# power-1.net
KiCad netlist of a schematic drawn in Altium Designer
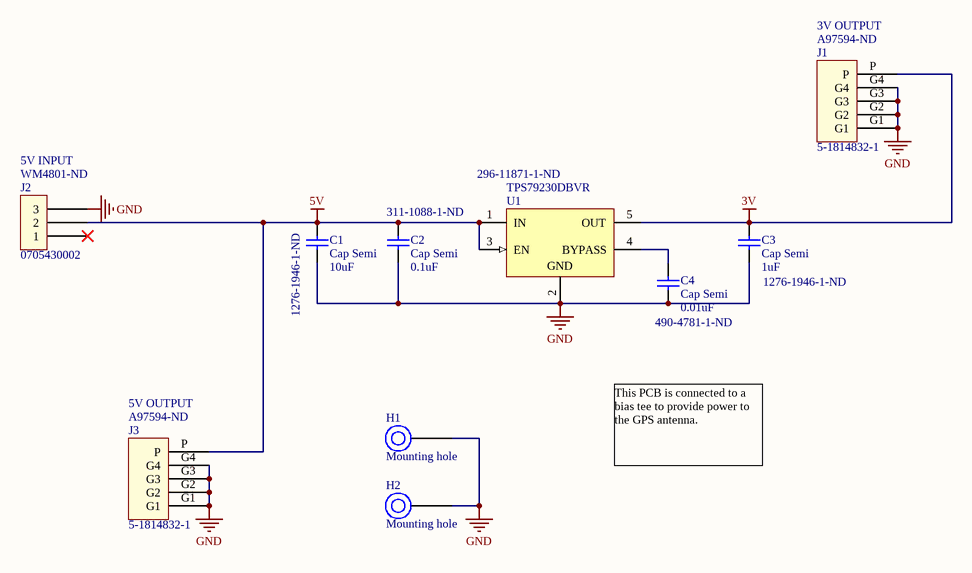
[diagram p0: power-1.SchDoc]

(export (version "E")
  (design (tool "Eeschema 10.0.6"))
  (components
    (comp (ref "C1")
      (value "Cap Semi")
      (footprint "1608[0603]")
      (description "Capacitor (Semiconductor SIM Model)")
      (fields
        (field (name "ALTIUM_VALUE") "10uF")
        (field (name "SUPPLIER PART NUMBER 1") "1276-1946-1-ND")
        (field (name "MANUFACTURER") "Samsung")
        (field (name "MANUFACTURER PART NUMBER") "CL10B105KP8NNNC")
        (field (name "PUBLISHER") "Altium Limited")
      )
      (libsource (lib "Miscellaneous Devices") (part "Cap Semi"))
    )
    (comp (ref "C2")
      (value "Cap Semi")
      (footprint "1608[0603]")
      (description "Capacitor (Semiconductor SIM Model)")
      (fields
        (field (name "ALTIUM_VALUE") "0.1uF")
        (field (name "SUPPLIER PART NUMBER 1") "311-1088-1-ND")
        (field (name "MANUFACTURER") "Yageo")
        (field (name "MANUFACTURER PART NUMBER") "CC0603KRX7R7BB104")
        (field (name "PUBLISHER") "Altium Limited")
      )
      (libsource (lib "Miscellaneous Devices") (part "Cap Semi"))
    )
    (comp (ref "C3")
      (value "Cap Semi")
      (footprint "1608[0603]")
      (description "Capacitor (Semiconductor SIM Model)")
      (fields
        (field (name "ALTIUM_VALUE") "1uF")
        (field (name "SUPPLIER PART NUMBER 1") "1276-1946-1-ND")
        (field (name "MANUFACTURER") "Samsung")
        (field (name "MANUFACTURER PART NUMBER") "CL10B105KP8NNNC")
        (field (name "PUBLISHER") "Altium Limited")
      )
      (libsource (lib "Miscellaneous Devices") (part "Cap Semi"))
    )
    (comp (ref "C4")
      (value "Cap Semi")
      (footprint "1608[0603]")
      (description "Capacitor (Semiconductor SIM Model)")
      (fields
        (field (name "ALTIUM_VALUE") "0.01uF")
        (field (name "SUPPLIER PART NUMBER 1") "490-4781-1-ND")
        (field (name "MANUFACTURER") "Murata")
        (field (name "MANUFACTURER PART NUMBER") "GCM188R72A103KA37D")
        (field (name "PUBLISHER") "Altium Limited")
      )
      (libsource (lib "Miscellaneous Devices") (part "Cap Semi"))
    )
    (comp (ref "H1")
      (value "Mounting hole")
      (footprint "M3 hole")
      (description "Mounting Hole")
      (libsource (lib "holes") (part "Mouting hole"))
    )
    (comp (ref "H2")
      (value "Mounting hole")
      (footprint "M3 hole")
      (description "Mounting Hole")
      (libsource (lib "holes") (part "Mouting hole"))
    )
    (comp (ref "J1")
      (value "5-1814832-1")
      (footprint "5-1814832-1")
      (fields
        (field (name "SUPPLIER PART NUMBER 1") "A97594-ND")
        (field (name "MANUFACTURER") "TE Connectivity")
      )
      (libsource (lib "TE") (part "5-1814832-1"))
    )
    (comp (ref "J2")
      (value "0705430002")
      (footprint "0705430002")
      (fields
        (field (name "SUPPLIER PART NUMBER 1") "WM4801-ND")
        (field (name "MANUFACTURER") "Molex")
        (field (name "MANUFACTURER PART NUMBER") "70543-0002")
      )
      (libsource (lib "molex") (part "0705430002"))
    )
    (comp (ref "J3")
      (value "5-1814832-1")
      (footprint "5-1814832-1")
      (fields
        (field (name "SUPPLIER PART NUMBER 1") "A97594-ND")
        (field (name "MANUFACTURER") "TE Connectivity")
      )
      (libsource (lib "TE") (part "5-1814832-1"))
    )
    (comp (ref "U1")
      (value "TPS79230DBVR")
      (footprint "DBV0005A_L")
      (fields
        (field (name "MANUFACTURER") "Texas Instruments")
        (field (name "SUPPLIER PART NUMBER 1") "296-11871-1-ND")
      )
      (libsource (lib "Altium Content Vault") (part "TI-TPS7XXXX-DBV5"))
    )
  )
  (nets
    (net (code "1") (name "3V") (class "Default")
      (node (ref "C3") (pin "2") (pinfunction "2_2") (pintype "passive"))
      (node (ref "J1") (pin "P") (pinfunction "P_P") (pintype "passive"))
      (node (ref "U1") (pin "5") (pinfunction "OUT_5") (pintype "power_in"))
    )
    (net (code "2") (name "5V") (class "Default")
      (node (ref "C1") (pin "2") (pinfunction "2_2") (pintype "passive"))
      (node (ref "C2") (pin "2") (pinfunction "2_2") (pintype "passive"))
      (node (ref "J2") (pin "2") (pinfunction "2_2") (pintype "passive"))
      (node (ref "J3") (pin "P") (pinfunction "P_P") (pintype "passive"))
      (node (ref "U1") (pin "1") (pinfunction "IN_1") (pintype "power_in"))
      (node (ref "U1") (pin "3") (pinfunction "EN_3") (pintype "input"))
    )
    (net (code "3") (name "GND") (class "Default")
      (node (ref "C1") (pin "1") (pinfunction "1_1") (pintype "passive"))
      (node (ref "C2") (pin "1") (pinfunction "1_1") (pintype "passive"))
      (node (ref "C3") (pin "1") (pinfunction "1_1") (pintype "passive"))
      (node (ref "C4") (pin "1") (pinfunction "1_1") (pintype "passive"))
      (node (ref "H1") (pin "1") (pinfunction "1_1") (pintype "passive"))
      (node (ref "H2") (pin "1") (pinfunction "1_1") (pintype "passive"))
      (node (ref "J1") (pin "G1") (pinfunction "G1_G1") (pintype "passive"))
      (node (ref "J1") (pin "G2") (pinfunction "G2_G2") (pintype "passive"))
      (node (ref "J1") (pin "G3") (pinfunction "G3_G3") (pintype "passive"))
      (node (ref "J1") (pin "G4") (pinfunction "G4_G4") (pintype "passive"))
      (node (ref "J2") (pin "3") (pinfunction "3_3") (pintype "passive"))
      (node (ref "J3") (pin "G1") (pinfunction "G1_G1") (pintype "passive"))
      (node (ref "J3") (pin "G2") (pinfunction "G2_G2") (pintype "passive"))
      (node (ref "J3") (pin "G3") (pinfunction "G3_G3") (pintype "passive"))
      (node (ref "J3") (pin "G4") (pinfunction "G4_G4") (pintype "passive"))
      (node (ref "U1") (pin "2") (pinfunction "GND_2") (pintype "power_in"))
    )
    (net (code "4") (name "Net-(U1-BYPASS)") (class "Default")
      (node (ref "C4") (pin "2") (pinfunction "2_2") (pintype "passive"))
      (node (ref "U1") (pin "4") (pinfunction "BYPASS_4") (pintype "passive"))
    )
    (net (code "5") (name "unconnected-(J2-Pad1)") (class "Default")
      (node (ref "J2") (pin "1") (pinfunction "1_1") (pintype "passive+no_connect"))
    )
  )
)
